# launch_stand_interface.net
KiCad netlist of a schematic drawn in Altium Designer
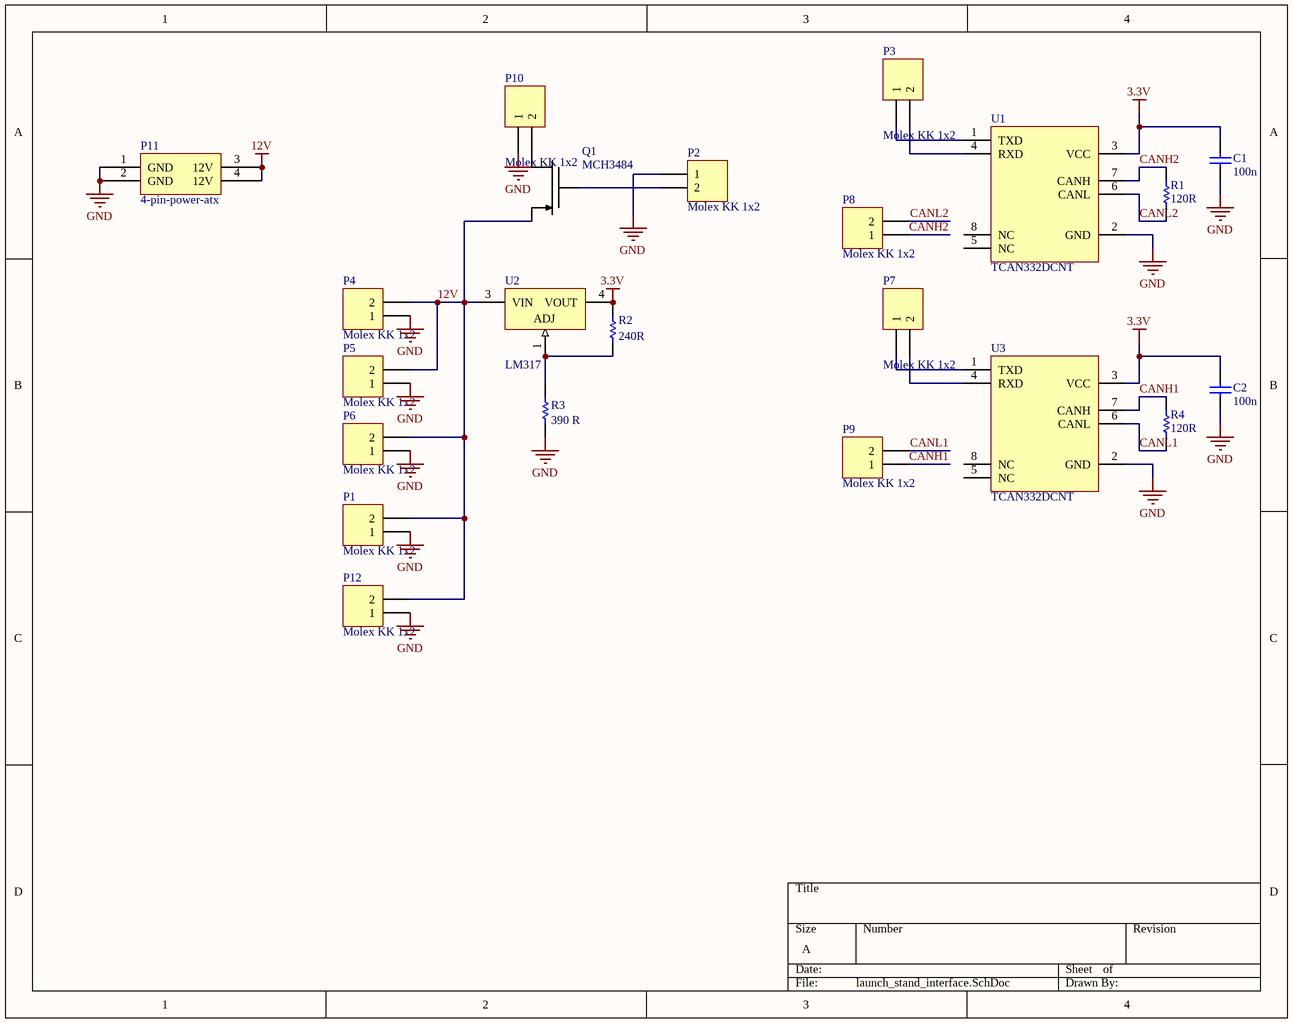
[diagram p0: launch_stand_interface.SchDoc]

(export (version "E")
  (design (tool "Eeschema 10.0.6"))
  (components
    (comp (ref "C1")
      (value "100n")
      (footprint "C0805")
      (description "0805 Capacitor")
      (libsource (lib "PARSEC") (part "C0805"))
    )
    (comp (ref "C2")
      (value "100n")
      (footprint "C0805")
      (description "0805 Capacitor")
      (libsource (lib "PARSEC") (part "C0805"))
    )
    (comp (ref "P1")
      (value "Molex KK 1x2")
      (footprint "Molex KK 2x1")
      (description "1x2 Molex KK Connector")
      (libsource (lib "PARSEC") (part "Molex KK 1x2"))
    )
    (comp (ref "P2")
      (value "Molex KK 1x2")
      (footprint "Molex KK 2x1")
      (description "1x2 Molex KK Connector")
      (libsource (lib "") (part "Molex KK 1x2_2"))
    )
    (comp (ref "P3")
      (value "Molex KK 1x2")
      (footprint "Molex KK 2x1")
      (description "1x2 Molex KK Connector")
      (libsource (lib "") (part "Molex KK 1x2_1"))
    )
    (comp (ref "P4")
      (value "Molex KK 1x2")
      (footprint "Molex KK 2x1")
      (description "1x2 Molex KK Connector")
      (libsource (lib "PARSEC") (part "Molex KK 1x2"))
    )
    (comp (ref "P5")
      (value "Molex KK 1x2")
      (footprint "Molex KK 2x1")
      (description "1x2 Molex KK Connector")
      (libsource (lib "PARSEC") (part "Molex KK 1x2"))
    )
    (comp (ref "P6")
      (value "Molex KK 1x2")
      (footprint "Molex KK 2x1")
      (description "1x2 Molex KK Connector")
      (libsource (lib "PARSEC") (part "Molex KK 1x2"))
    )
    (comp (ref "P7")
      (value "Molex KK 1x2")
      (footprint "Molex KK 2x1")
      (description "1x2 Molex KK Connector")
      (libsource (lib "") (part "Molex KK 1x2_1"))
    )
    (comp (ref "P8")
      (value "Molex KK 1x2")
      (footprint "Molex KK 2x1")
      (description "1x2 Molex KK Connector")
      (libsource (lib "PARSEC") (part "Molex KK 1x2"))
    )
    (comp (ref "P9")
      (value "Molex KK 1x2")
      (footprint "Molex KK 2x1")
      (description "1x2 Molex KK Connector")
      (libsource (lib "PARSEC") (part "Molex KK 1x2"))
    )
    (comp (ref "P10")
      (value "Molex KK 1x2")
      (footprint "Molex KK 2x1")
      (description "1x2 Molex KK Connector")
      (libsource (lib "") (part "Molex KK 1x2_1"))
    )
    (comp (ref "P11")
      (value "4-pin-power-atx")
      (footprint "4-pin-atx")
      (libsource (lib "PARSEC") (part "4-pin-power-atx"))
    )
    (comp (ref "P12")
      (value "Molex KK 1x2")
      (footprint "Molex KK 2x1")
      (description "1x2 Molex KK Connector")
      (libsource (lib "PARSEC") (part "Molex KK 1x2"))
    )
    (comp (ref "Q1")
      (value "MCH3484")
      (footprint "SC-70FL/MCPH3")
      (libsource (lib "PARSEC") (part "MCH3484"))
    )
    (comp (ref "R1")
      (value "120R")
      (footprint "R0805")
      (description "RESISTOR 0805")
      (libsource (lib "PARSEC") (part "R0805"))
    )
    (comp (ref "R2")
      (value "240R")
      (footprint "R0805")
      (description "RESISTOR 0805")
      (libsource (lib "*") (part "R0805"))
    )
    (comp (ref "R3")
      (value "390 R")
      (footprint "R0805")
      (description "RESISTOR 0805")
      (libsource (lib "*") (part "R0805"))
    )
    (comp (ref "R4")
      (value "120R")
      (footprint "R0805")
      (description "RESISTOR 0805")
      (libsource (lib "PARSEC") (part "R0805"))
    )
    (comp (ref "U1")
      (value "TCAN332DCNT")
      (footprint "SOT-23-8")
      (description "IC TXRX CAN 3.3V SOT23-8")
      (libsource (lib "PARSEC") (part "TCAN332DCNT"))
    )
    (comp (ref "U2")
      (value "LM317")
      (footprint "D-PAK")
      (description "Linear Voltage Regulator")
      (libsource (lib "PARSEC") (part "LM317"))
    )
    (comp (ref "U3")
      (value "TCAN332DCNT")
      (footprint "SOT-23-8")
      (description "IC TXRX CAN 3.3V SOT23-8")
      (libsource (lib "PARSEC") (part "TCAN332DCNT"))
    )
  )
  (nets
    (net (code "1") (name "/CANH1") (class "Default")
      (node (ref "P9") (pin "1") (pinfunction "1_1") (pintype "passive"))
      (node (ref "R4") (pin "2") (pinfunction "2_2") (pintype "passive"))
      (node (ref "U3") (pin "7") (pinfunction "CANH_7") (pintype "passive"))
    )
    (net (code "2") (name "/CANH2") (class "Default")
      (node (ref "P8") (pin "1") (pinfunction "1_1") (pintype "passive"))
      (node (ref "R1") (pin "2") (pinfunction "2_2") (pintype "passive"))
      (node (ref "U1") (pin "7") (pinfunction "CANH_7") (pintype "passive"))
    )
    (net (code "3") (name "/CANL1") (class "Default")
      (node (ref "P9") (pin "2") (pinfunction "2_2") (pintype "passive"))
      (node (ref "R4") (pin "1") (pinfunction "1_1") (pintype "passive"))
      (node (ref "U3") (pin "6") (pinfunction "CANL_6") (pintype "passive"))
    )
    (net (code "4") (name "/CANL2") (class "Default")
      (node (ref "P8") (pin "2") (pinfunction "2_2") (pintype "passive"))
      (node (ref "R1") (pin "1") (pinfunction "1_1") (pintype "passive"))
      (node (ref "U1") (pin "6") (pinfunction "CANL_6") (pintype "passive"))
    )
    (net (code "5") (name "3.3V") (class "Default")
      (node (ref "C1") (pin "1") (pinfunction "1_1") (pintype "passive"))
      (node (ref "C2") (pin "1") (pinfunction "1_1") (pintype "passive"))
      (node (ref "R2") (pin "2") (pinfunction "2_2") (pintype "passive"))
      (node (ref "U1") (pin "3") (pinfunction "VCC_3") (pintype "passive"))
      (node (ref "U2") (pin "4") (pinfunction "VOUT_4") (pintype "power_in"))
      (node (ref "U3") (pin "3") (pinfunction "VCC_3") (pintype "passive"))
    )
    (net (code "6") (name "12V") (class "Default")
      (node (ref "P1") (pin "2") (pinfunction "2_2") (pintype "passive"))
      (node (ref "P11") (pin "3") (pinfunction "12V_3") (pintype "passive"))
      (node (ref "P11") (pin "4") (pinfunction "12V_4") (pintype "passive"))
      (node (ref "P12") (pin "2") (pinfunction "2_2") (pintype "passive"))
      (node (ref "P4") (pin "2") (pinfunction "2_2") (pintype "passive"))
      (node (ref "P5") (pin "2") (pinfunction "2_2") (pintype "passive"))
      (node (ref "P6") (pin "2") (pinfunction "2_2") (pintype "passive"))
      (node (ref "Q1") (pin "2") (pinfunction "Source_2") (pintype "passive"))
      (node (ref "U2") (pin "3") (pinfunction "VIN_3") (pintype "power_in"))
    )
    (net (code "7") (name "GND") (class "Default")
      (node (ref "C1") (pin "2") (pinfunction "2_2") (pintype "passive"))
      (node (ref "C2") (pin "2") (pinfunction "2_2") (pintype "passive"))
      (node (ref "P1") (pin "1") (pinfunction "1_1") (pintype "passive"))
      (node (ref "P10") (pin "1") (pinfunction "1_1") (pintype "passive"))
      (node (ref "P11") (pin "1") (pinfunction "GND_1") (pintype "passive"))
      (node (ref "P11") (pin "2") (pinfunction "GND_2") (pintype "passive"))
      (node (ref "P12") (pin "1") (pinfunction "1_1") (pintype "passive"))
      (node (ref "P2") (pin "1") (pinfunction "1_1") (pintype "passive"))
      (node (ref "P4") (pin "1") (pinfunction "1_1") (pintype "passive"))
      (node (ref "P5") (pin "1") (pinfunction "1_1") (pintype "passive"))
      (node (ref "P6") (pin "1") (pinfunction "1_1") (pintype "passive"))
      (node (ref "R3") (pin "1") (pinfunction "1_1") (pintype "passive"))
      (node (ref "U1") (pin "2") (pinfunction "GND_2") (pintype "passive"))
      (node (ref "U3") (pin "2") (pinfunction "GND_2") (pintype "passive"))
    )
    (net (code "8") (name "Net-(Q1-Drain)") (class "Default")
      (node (ref "P10") (pin "2") (pinfunction "2_2") (pintype "passive"))
      (node (ref "Q1") (pin "3") (pinfunction "Drain_3") (pintype "passive"))
    )
    (net (code "9") (name "Net-(Q1-Gate)") (class "Default")
      (node (ref "P2") (pin "2") (pinfunction "2_2") (pintype "passive"))
      (node (ref "Q1") (pin "1") (pinfunction "Gate_1") (pintype "passive"))
    )
    (net (code "10") (name "Net-(U1-RXD)") (class "Default")
      (node (ref "P3") (pin "2") (pinfunction "2_2") (pintype "passive"))
      (node (ref "U1") (pin "4") (pinfunction "RXD_4") (pintype "passive"))
    )
    (net (code "11") (name "Net-(U1-TXD)") (class "Default")
      (node (ref "P3") (pin "1") (pinfunction "1_1") (pintype "passive"))
      (node (ref "U1") (pin "1") (pinfunction "TXD_1") (pintype "passive"))
    )
    (net (code "12") (name "Net-(U2-ADJ)") (class "Default")
      (node (ref "R2") (pin "1") (pinfunction "1_1") (pintype "passive"))
      (node (ref "R3") (pin "2") (pinfunction "2_2") (pintype "passive"))
      (node (ref "U2") (pin "1") (pinfunction "ADJ_1") (pintype "input"))
    )
    (net (code "13") (name "Net-(U3-RXD)") (class "Default")
      (node (ref "P7") (pin "2") (pinfunction "2_2") (pintype "passive"))
      (node (ref "U3") (pin "4") (pinfunction "RXD_4") (pintype "passive"))
    )
    (net (code "14") (name "Net-(U3-TXD)") (class "Default")
      (node (ref "P7") (pin "1") (pinfunction "1_1") (pintype "passive"))
      (node (ref "U3") (pin "1") (pinfunction "TXD_1") (pintype "passive"))
    )
    (net (code "15") (name "unconnected-(U1-NC-Pad5)") (class "Default")
      (node (ref "U1") (pin "5") (pinfunction "NC_5") (pintype "passive"))
    )
    (net (code "16") (name "unconnected-(U1-NC-Pad8)") (class "Default")
      (node (ref "U1") (pin "8") (pinfunction "NC_8") (pintype "passive"))
    )
    (net (code "17") (name "unconnected-(U3-NC-Pad5)") (class "Default")
      (node (ref "U3") (pin "5") (pinfunction "NC_5") (pintype "passive"))
    )
    (net (code "18") (name "unconnected-(U3-NC-Pad8)") (class "Default")
      (node (ref "U3") (pin "8") (pinfunction "NC_8") (pintype "passive"))
    )
  )
)
